# 02_Input_Connectors.net
KiCad netlist of a schematic drawn in Altium Designer
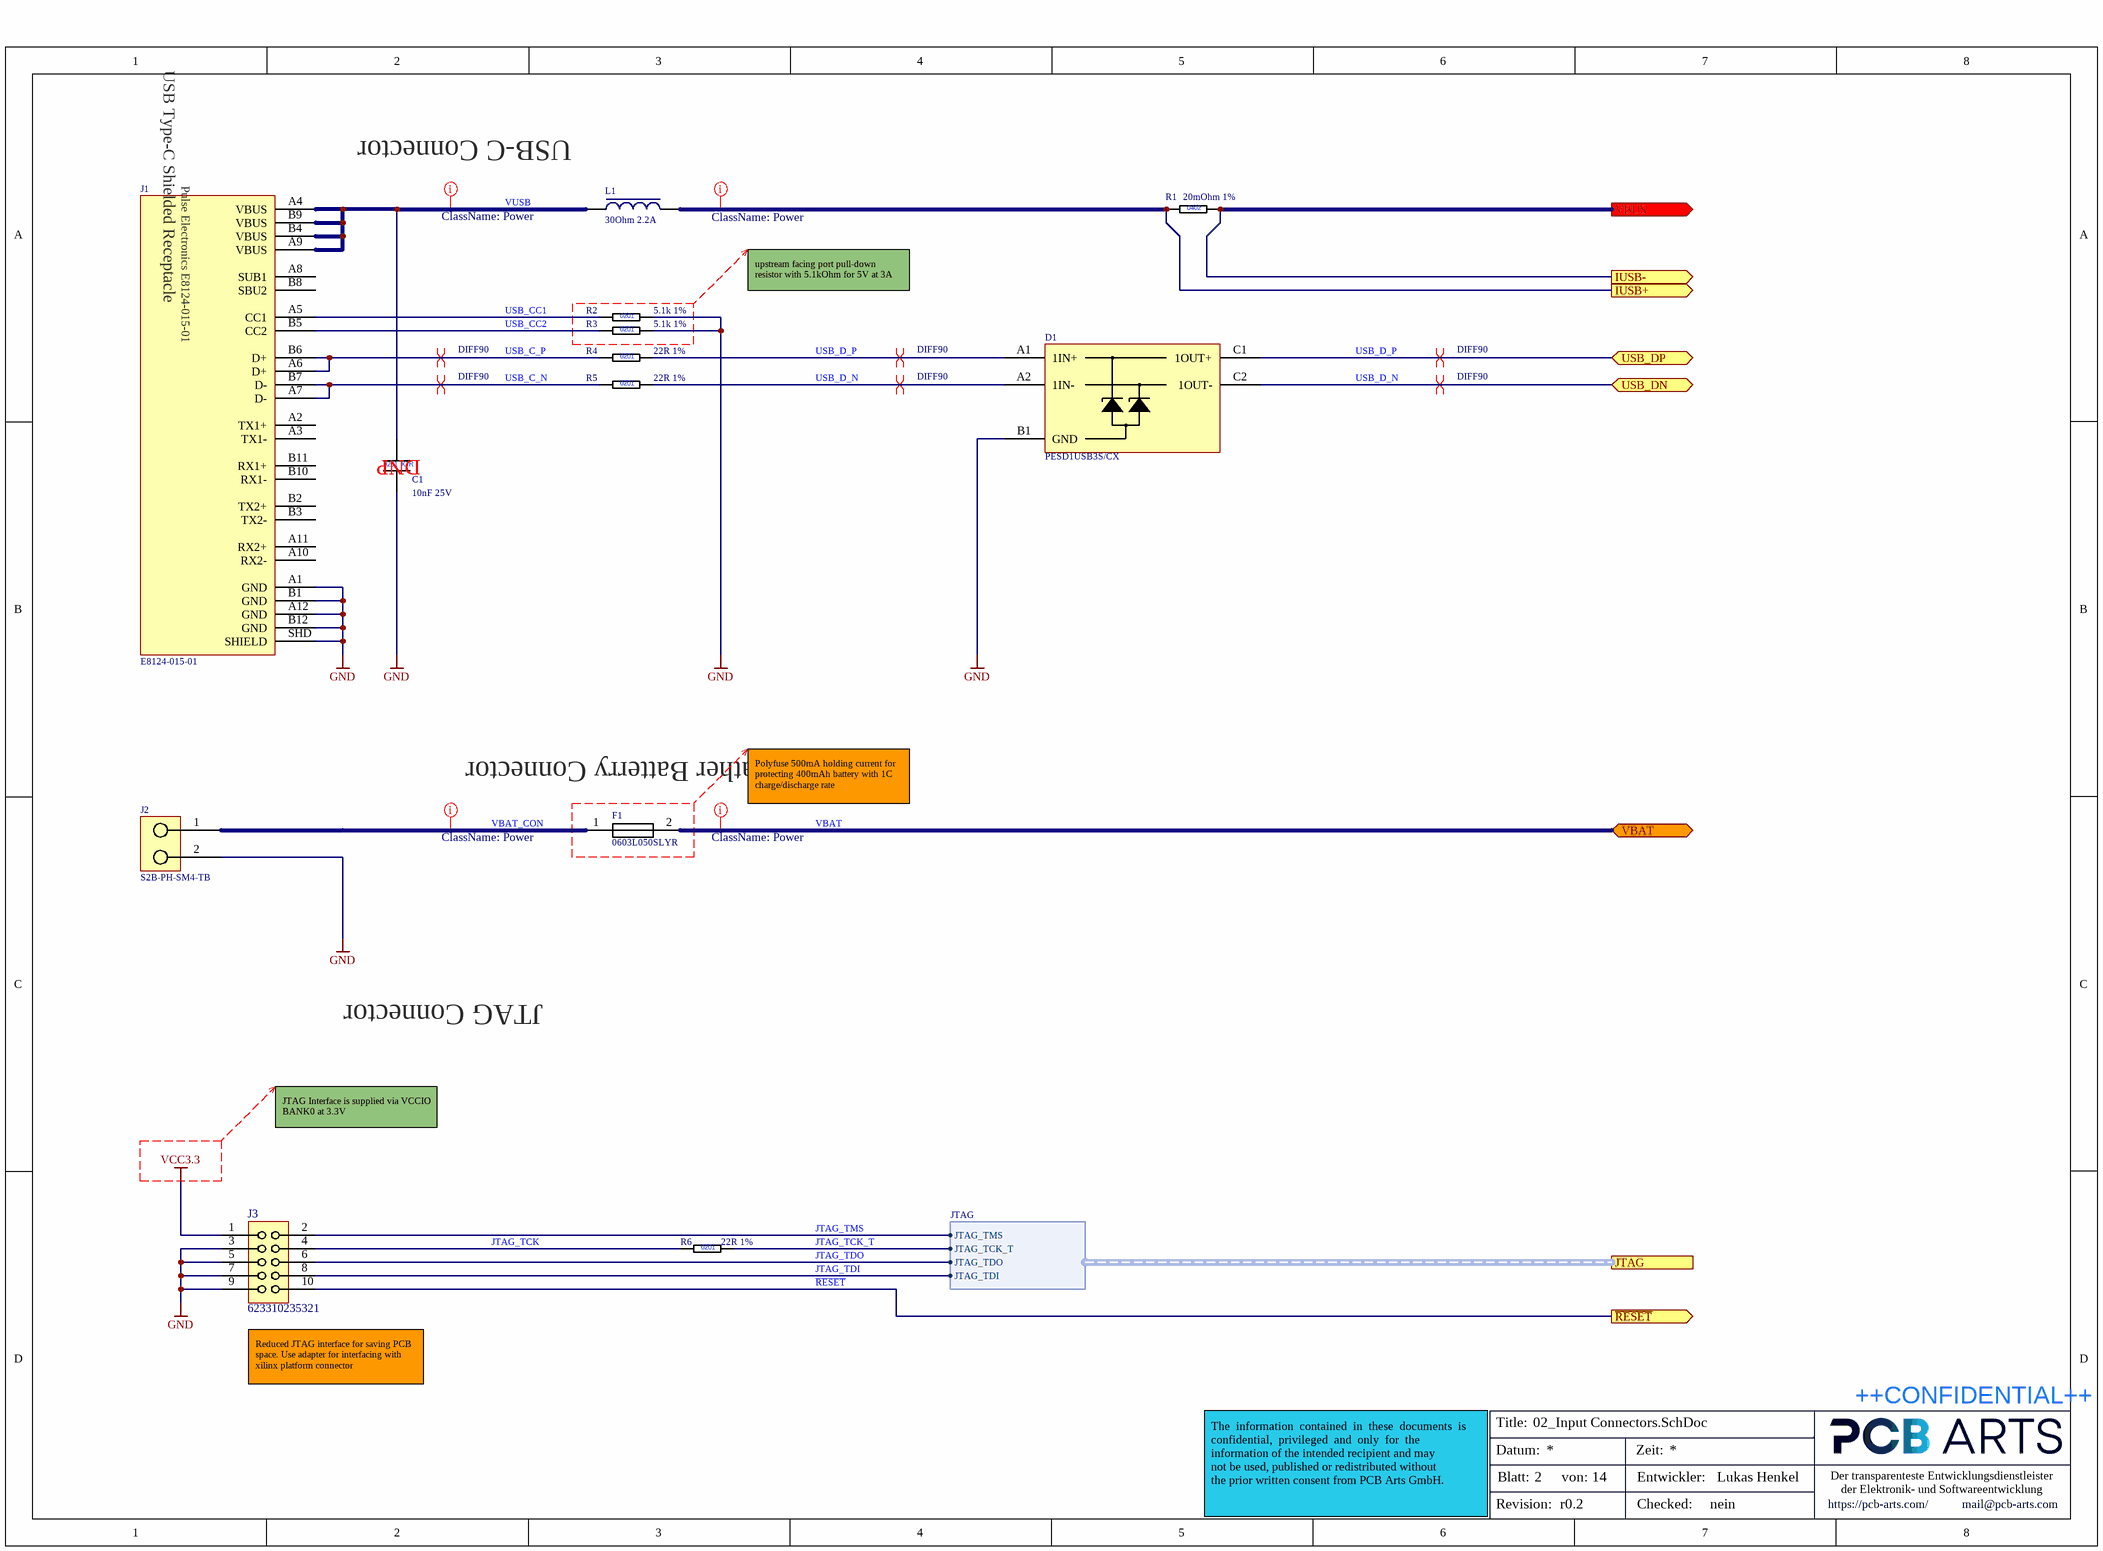
[diagram p0: 02_Input Connectors.SchDoc]

(export (version "E")
  (design (tool "Eeschema 10.0.6"))
  (components
    (comp (ref "C1")
      (value "10nF 25V")
      (footprint "Zynq-Feather-HD:CAPC0603X03L")
      (description "Multilayer Ceramic Capacitors MLCC - SMD/SMT 0201 25VDC")
      (libsource (lib "Zynq-Feather-HD") (part "CAP_0201_10nF_25V"))
    )
    (comp (ref "D1")
      (value "PESD1USB3S/CX")
      (footprint "Zynq-Feather-HD:BGAS5C40P2X3_77X117X60")
      (description "ESD Suppressors / TVS Diodes PESD1USB3S/NAX000")
      (libsource (lib "Zynq-Feather-HD") (part "PESD1USB3S/CX_ESD Suppressors / TVS Diodes PESD1USB3S/NAX000"))
    )
    (comp (ref "F1")
      (value "0603L050SLYR")
      (footprint "Zynq-Feather-HD:0603L050SLYR")
      (description "Resettable Fuses - PPTC 6V POLYFUSE 0603 LoRho SL 0.50A")
      (libsource (lib "Zynq-Feather-HD") (part "0603L050SLYR_PPTC 6V POLYFUSE 0603 LoRho SL 0.50A"))
    )
    (comp (ref "J1")
      (value "E8124-015-01")
      (footprint "Zynq-Feather-HD:E8124-015-01")
      (description "USB-Stecker USB 3.1 TYPE C 10G Top Mount")
      (libsource (lib "Zynq-Feather-HD") (part "E8124-015-01_USB Type-C Receptacle"))
    )
    (comp (ref "J2")
      (value "S2B-PH-SM4-TB")
      (footprint "Zynq-Feather-HD:S2B-PH-SM4-TB")
      (description "JST Automotive 2mm pitch crimp style connector")
      (libsource (lib "Zynq-Feather-HD") (part "S2B-PH-SM4-TB JST Automotive 2mm pitch connector"))
    )
    (comp (ref "J3")
      (value "623310235321")
      (footprint "Zynq-Feather-HD:623310235321_NBE")
      (description "WR-PHD 1.27 mm SMT Dual Socket Header, H=2.20 mm")
      (libsource (lib "Zynq-Feather-HD") (part "623310235321_WR-PHD 1.27 mm SMT Dual Socket Header"))
    )
    (comp (ref "L1")
      (value "30Ohm 2.2A")
      (footprint "Zynq-Feather-HD:INDC1005X06L")
      (description "Ferrite Bead 0402 30Ohm 2.2A 25%")
      (fields (field (name "MANUFACTURER") "Murata Electronics"))
      (libsource (lib "Zynq-Feather-HD") (part "FLT_0402_30Ohm_2.2A"))
    )
    (comp (ref "R1")
      (value "20mOhm 1%")
      (footprint "Zynq-Feather-HD:RESC1005X04L")
      (description "Thick Film Resistors - SMD 20mOHM 1%")
      (libsource (lib "Zynq-Feather-HD") (part "RES_0402_20mR_1%"))
    )
    (comp (ref "R2")
      (value "5.1k 1%")
      (footprint "Zynq-Feather-HD:RESC0603X03L")
      (description "Thick Film Resistors - SMD 5.1K OHM 1%")
      (libsource (lib "Zynq-Feather-HD") (part "RES_0201_5.1k_1%"))
    )
    (comp (ref "R3")
      (value "5.1k 1%")
      (footprint "Zynq-Feather-HD:RESC0603X03L")
      (description "Thick Film Resistors - SMD 5.1K OHM 1%")
      (libsource (lib "Zynq-Feather-HD") (part "RES_0201_5.1k_1%"))
    )
    (comp (ref "R4")
      (value "22R 1%")
      (footprint "Zynq-Feather-HD:RESC0603X03L")
      (description "Thick Film Resistors - SMD 22R OHM 1%")
      (libsource (lib "Zynq-Feather-HD") (part "RES_0201_22R_1%"))
    )
    (comp (ref "R5")
      (value "22R 1%")
      (footprint "Zynq-Feather-HD:RESC0603X03L")
      (description "Thick Film Resistors - SMD 22R OHM 1%")
      (libsource (lib "Zynq-Feather-HD") (part "RES_0201_22R_1%"))
    )
    (comp (ref "R6")
      (value "22R 1%")
      (footprint "Zynq-Feather-HD:RESC0603X03L")
      (description "Thick Film Resistors - SMD 22R OHM 1%")
      (libsource (lib "Zynq-Feather-HD") (part "RES_0201_22R_1%"))
    )
  )
  (nets
    (net (code "2") (name "/IUSB+") (class "Default")
      (node (ref "L1") (pin "1") (pinfunction "1_1") (pintype "passive"))
      (node (ref "R1") (pin "1") (pinfunction "1_1") (pintype "passive"))
    )
    (net (code "3") (name "/IUSB-") (class "Default")
      (node (ref "R1") (pin "2") (pinfunction "2_2") (pintype "passive"))
    )
    (net (code "4") (name "/JTAG_TCK") (class "Default")
      (node (ref "J3") (pin "4") (pinfunction "4_4") (pintype "passive"))
      (node (ref "R6") (pin "1") (pinfunction "1_1") (pintype "passive"))
    )
    (net (code "5") (name "/JTAG_TCK_T") (class "Default")
      (node (ref "R6") (pin "2") (pinfunction "2_2") (pintype "passive"))
    )
    (net (code "6") (name "/JTAG_TDI") (class "Default")
      (node (ref "J3") (pin "8") (pinfunction "8_8") (pintype "passive"))
    )
    (net (code "7") (name "/JTAG_TDO") (class "Default")
      (node (ref "J3") (pin "6") (pinfunction "6_6") (pintype "passive"))
    )
    (net (code "8") (name "/JTAG_TMS") (class "Default")
      (node (ref "J3") (pin "2") (pinfunction "2_2") (pintype "passive"))
    )
    (net (code "9") (name "/USB_CC1") (class "Default")
      (node (ref "J1") (pin "A5") (pinfunction "CC1_A5") (pintype "passive"))
      (node (ref "R2") (pin "1") (pinfunction "1_1") (pintype "passive"))
    )
    (net (code "10") (name "/USB_CC2") (class "Default")
      (node (ref "J1") (pin "B5") (pinfunction "CC2_B5") (pintype "passive"))
      (node (ref "R3") (pin "1") (pinfunction "1_1") (pintype "passive"))
    )
    (net (code "11") (name "/USB_C_N") (class "Default")
      (node (ref "J1") (pin "A7") (pinfunction "D-_A7") (pintype "passive"))
      (node (ref "J1") (pin "B7") (pinfunction "D-_B7") (pintype "passive"))
      (node (ref "R5") (pin "1") (pinfunction "1_1") (pintype "passive"))
    )
    (net (code "12") (name "/USB_C_P") (class "Default")
      (node (ref "J1") (pin "A6") (pinfunction "D+_A6") (pintype "passive"))
      (node (ref "J1") (pin "B6") (pinfunction "D+_B6") (pintype "passive"))
      (node (ref "R4") (pin "1") (pinfunction "1_1") (pintype "passive"))
    )
    (net (code "13") (name "/USB_D_N") (class "Default")
      (node (ref "D1") (pin "A2") (pinfunction "1IN-_A2") (pintype "passive"))
      (node (ref "D1") (pin "C2") (pinfunction "1OUT-_C2") (pintype "passive"))
      (node (ref "R5") (pin "2") (pinfunction "2_2") (pintype "passive"))
    )
    (net (code "14") (name "/USB_D_P") (class "Default")
      (node (ref "D1") (pin "A1") (pinfunction "1IN+_A1") (pintype "passive"))
      (node (ref "D1") (pin "C1") (pinfunction "1OUT+_C1") (pintype "passive"))
      (node (ref "R4") (pin "2") (pinfunction "2_2") (pintype "passive"))
    )
    (net (code "15") (name "/VBAT") (class "Default")
      (node (ref "F1") (pin "2") (pinfunction "2_2") (pintype "passive"))
    )
    (net (code "16") (name "/VBAT_CON") (class "Default")
      (node (ref "F1") (pin "1") (pinfunction "1_1") (pintype "passive"))
      (node (ref "J2") (pin "1") (pinfunction "1_1") (pintype "passive"))
    )
    (net (code "17") (name "/VUSB") (class "Default")
      (node (ref "C1") (pin "1") (pinfunction "1_1") (pintype "passive"))
      (node (ref "J1") (pin "A4") (pinfunction "VBUS_A4") (pintype "passive"))
      (node (ref "J1") (pin "A9") (pinfunction "VBUS_A9") (pintype "passive"))
      (node (ref "J1") (pin "B4") (pinfunction "VBUS_B4") (pintype "passive"))
      (node (ref "J1") (pin "B9") (pinfunction "VBUS_B9") (pintype "passive"))
      (node (ref "L1") (pin "2") (pinfunction "2_2") (pintype "passive"))
    )
    (net (code "19") (name "/~{RESET}") (class "Default")
      (node (ref "J3") (pin "10") (pinfunction "10_10") (pintype "passive"))
    )
    (net (code "20") (name "GND") (class "Default")
      (node (ref "C1") (pin "2") (pinfunction "2_2") (pintype "passive"))
      (node (ref "D1") (pin "B1") (pinfunction "GND_B1") (pintype "passive"))
      (node (ref "J1") (pin "A1") (pinfunction "GND_A1") (pintype "passive"))
      (node (ref "J1") (pin "A12") (pinfunction "GND_A12") (pintype "passive"))
      (node (ref "J1") (pin "B1") (pinfunction "GND_B1") (pintype "passive"))
      (node (ref "J1") (pin "B12") (pinfunction "GND_B12") (pintype "passive"))
      (node (ref "J1") (pin "SHD") (pinfunction "SHIELD_SHD") (pintype "passive"))
      (node (ref "J2") (pin "2") (pinfunction "2_2") (pintype "passive"))
      (node (ref "J3") (pin "3") (pinfunction "3_3") (pintype "passive"))
      (node (ref "J3") (pin "5") (pinfunction "5_5") (pintype "passive"))
      (node (ref "J3") (pin "7") (pinfunction "7_7") (pintype "passive"))
      (node (ref "J3") (pin "9") (pinfunction "9_9") (pintype "passive"))
      (node (ref "R2") (pin "2") (pinfunction "2_2") (pintype "passive"))
      (node (ref "R3") (pin "2") (pinfunction "2_2") (pintype "passive"))
    )
    (net (code "21") (name "VCC3.3") (class "Default")
      (node (ref "J3") (pin "1") (pinfunction "1_1") (pintype "passive"))
    )
    (net (code "22") (name "unconnected-(J1-RX1+-PadB11)") (class "Default")
      (node (ref "J1") (pin "B11") (pinfunction "RX1+_B11") (pintype "passive"))
    )
    (net (code "23") (name "unconnected-(J1-RX1--PadB10)") (class "Default")
      (node (ref "J1") (pin "B10") (pinfunction "RX1-_B10") (pintype "passive"))
    )
    (net (code "24") (name "unconnected-(J1-RX2+-PadA11)") (class "Default")
      (node (ref "J1") (pin "A11") (pinfunction "RX2+_A11") (pintype "passive"))
    )
    (net (code "25") (name "unconnected-(J1-RX2--PadA10)") (class "Default")
      (node (ref "J1") (pin "A10") (pinfunction "RX2-_A10") (pintype "passive"))
    )
    (net (code "26") (name "unconnected-(J1-SBU2-PadB8)") (class "Default")
      (node (ref "J1") (pin "B8") (pinfunction "SBU2_B8") (pintype "passive"))
    )
    (net (code "27") (name "unconnected-(J1-SUB1-PadA8)") (class "Default")
      (node (ref "J1") (pin "A8") (pinfunction "SUB1_A8") (pintype "passive"))
    )
    (net (code "28") (name "unconnected-(J1-TX1+-PadA2)") (class "Default")
      (node (ref "J1") (pin "A2") (pinfunction "TX1+_A2") (pintype "passive"))
    )
    (net (code "29") (name "unconnected-(J1-TX1--PadA3)") (class "Default")
      (node (ref "J1") (pin "A3") (pinfunction "TX1-_A3") (pintype "passive"))
    )
    (net (code "30") (name "unconnected-(J1-TX2+-PadB2)") (class "Default")
      (node (ref "J1") (pin "B2") (pinfunction "TX2+_B2") (pintype "passive"))
    )
    (net (code "31") (name "unconnected-(J1-TX2--PadB3)") (class "Default")
      (node (ref "J1") (pin "B3") (pinfunction "TX2-_B3") (pintype "passive"))
    )
  )
)
